# temperatur_sensor_childboard_v1.net
KiCad netlist of a schematic drawn in EAGLE
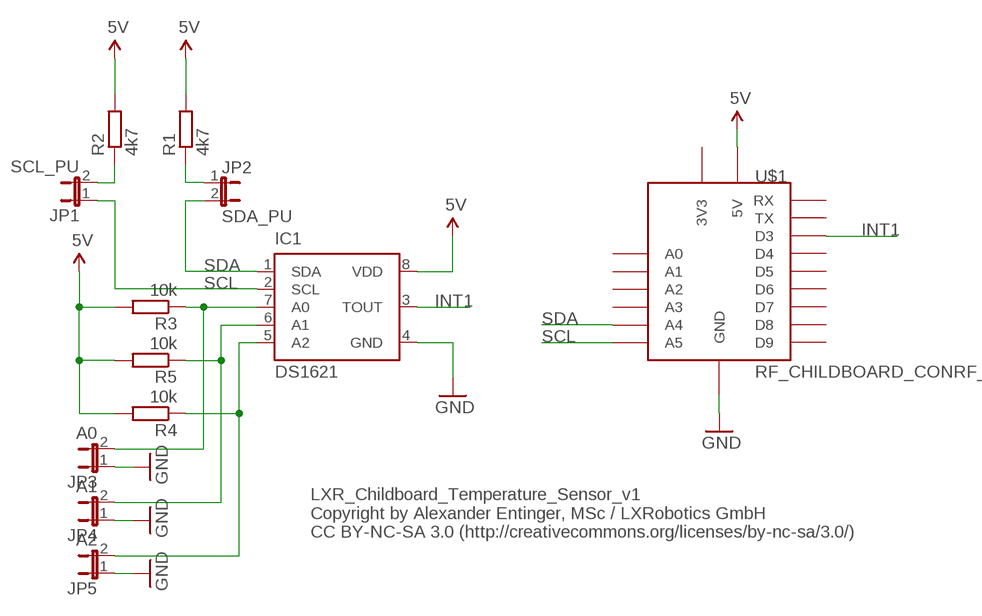
[diagram p0: schematic, sheet 1]

(export (version "E")
  (design (tool "Eeschema 10.0.6"))
  (components
    (comp (ref "IC1")
      (value "DS1621")
      (footprint "eagle-import:DIL08")
      (libsource (lib "eagle-import") (part "DS1621"))
    )
    (comp (ref "JP1")
      (value "SCL_PU")
      (footprint "eagle-import:JP1")
      (libsource (lib "eagle-import") (part "JP1E"))
    )
    (comp (ref "JP2")
      (value "SDA_PU")
      (footprint "eagle-import:JP1")
      (libsource (lib "eagle-import") (part "JP1E"))
    )
    (comp (ref "JP3")
      (value "A0")
      (footprint "eagle-import:JP1")
      (libsource (lib "eagle-import") (part "JP1E"))
    )
    (comp (ref "JP4")
      (value "A1")
      (footprint "eagle-import:JP1")
      (libsource (lib "eagle-import") (part "JP1E"))
    )
    (comp (ref "JP5")
      (value "A2")
      (footprint "eagle-import:JP1")
      (libsource (lib "eagle-import") (part "JP1E"))
    )
    (comp (ref "R1")
      (value "4k7")
      (footprint "eagle-import:0207_7")
      (libsource (lib "eagle-import") (part "R-EU_0207/7"))
    )
    (comp (ref "R2")
      (value "4k7")
      (footprint "eagle-import:0207_7")
      (libsource (lib "eagle-import") (part "R-EU_0207/7"))
    )
    (comp (ref "R3")
      (value "10k")
      (footprint "eagle-import:0207_7")
      (libsource (lib "eagle-import") (part "R-EU_0207/7"))
    )
    (comp (ref "R4")
      (value "10k")
      (footprint "eagle-import:0207_7")
      (libsource (lib "eagle-import") (part "R-EU_0207/7"))
    )
    (comp (ref "R5")
      (value "10k")
      (footprint "eagle-import:0207_7")
      (libsource (lib "eagle-import") (part "R-EU_0207/7"))
    )
    (comp (ref "U$1")
      (value "RF_CHILDBOARD_CONRF_C")
      (footprint "eagle-import:RF_CHILDBOARD_CON")
      (libsource (lib "eagle-import") (part "RF_CHILDBOARD_CONRF_C"))
    )
  )
  (nets
    (net (code "1") (name "/INT1") (class "Default")
      (node (ref "IC1") (pin "3") (pinfunction "TOUT_3") (pintype "output"))
      (node (ref "U$1") (pin "D3") (pinfunction "D3_D3") (pintype "bidirectional"))
    )
    (net (code "2") (name "/SCL") (class "Default")
      (node (ref "IC1") (pin "2") (pinfunction "SCL_2") (pintype "input"))
      (node (ref "JP1") (pin "1") (pinfunction "1_1") (pintype "passive"))
      (node (ref "U$1") (pin "A5") (pinfunction "A5_A5") (pintype "bidirectional"))
    )
    (net (code "3") (name "/SDA") (class "Default")
      (node (ref "IC1") (pin "1") (pinfunction "SDA_1") (pintype "bidirectional"))
      (node (ref "JP2") (pin "2") (pinfunction "2_2") (pintype "passive"))
      (node (ref "U$1") (pin "A4") (pinfunction "A4_A4") (pintype "bidirectional"))
    )
    (net (code "4") (name "5V") (class "Default")
      (node (ref "IC1") (pin "8") (pinfunction "VDD_8") (pintype "power_in"))
      (node (ref "R1") (pin "2") (pinfunction "2_2") (pintype "passive"))
      (node (ref "R2") (pin "2") (pinfunction "2_2") (pintype "passive"))
      (node (ref "R3") (pin "2") (pinfunction "2_2") (pintype "passive"))
      (node (ref "R4") (pin "2") (pinfunction "2_2") (pintype "passive"))
      (node (ref "R5") (pin "2") (pinfunction "2_2") (pintype "passive"))
      (node (ref "U$1") (pin "5V") (pinfunction "5V_5V") (pintype "bidirectional"))
    )
    (net (code "5") (name "GND") (class "Default")
      (node (ref "IC1") (pin "4") (pinfunction "GND_4") (pintype "power_in"))
      (node (ref "JP3") (pin "1") (pinfunction "1_1") (pintype "passive"))
      (node (ref "JP4") (pin "1") (pinfunction "1_1") (pintype "passive"))
      (node (ref "JP5") (pin "1") (pinfunction "1_1") (pintype "passive"))
      (node (ref "U$1") (pin "GND") (pinfunction "GND_GND") (pintype "bidirectional"))
      (node (ref "U$1") (pin "GND1") (pinfunction "GND_GND1") (pintype "bidirectional"))
      (node (ref "U$1") (pin "GND2") (pinfunction "GND_GND2") (pintype "bidirectional"))
    )
    (net (code "6") (name "Net-(IC1-A0)") (class "Default")
      (node (ref "IC1") (pin "7") (pinfunction "A0_7") (pintype "input"))
      (node (ref "JP3") (pin "2") (pinfunction "2_2") (pintype "passive"))
      (node (ref "R3") (pin "1") (pinfunction "1_1") (pintype "passive"))
    )
    (net (code "7") (name "Net-(IC1-A1)") (class "Default")
      (node (ref "IC1") (pin "6") (pinfunction "A1_6") (pintype "input"))
      (node (ref "JP4") (pin "2") (pinfunction "2_2") (pintype "passive"))
      (node (ref "R5") (pin "1") (pinfunction "1_1") (pintype "passive"))
    )
    (net (code "8") (name "Net-(IC1-A2)") (class "Default")
      (node (ref "IC1") (pin "5") (pinfunction "A2_5") (pintype "input"))
      (node (ref "JP5") (pin "2") (pinfunction "2_2") (pintype "passive"))
      (node (ref "R4") (pin "1") (pinfunction "1_1") (pintype "passive"))
    )
    (net (code "9") (name "Net-(JP1-Pad2)") (class "Default")
      (node (ref "JP1") (pin "2") (pinfunction "2_2") (pintype "passive"))
      (node (ref "R2") (pin "1") (pinfunction "1_1") (pintype "passive"))
    )
    (net (code "10") (name "Net-(JP2-Pad1)") (class "Default")
      (node (ref "JP2") (pin "1") (pinfunction "1_1") (pintype "passive"))
      (node (ref "R1") (pin "1") (pinfunction "1_1") (pintype "passive"))
    )
    (net (code "11") (name "unconnected-(U$1-Pad3V3)") (class "Default")
      (node (ref "U$1") (pin "3V3") (pinfunction "3V3_3V3") (pintype "bidirectional"))
    )
    (net (code "12") (name "unconnected-(U$1-PadA0)") (class "Default")
      (node (ref "U$1") (pin "A0") (pinfunction "A0_A0") (pintype "bidirectional"))
    )
    (net (code "13") (name "unconnected-(U$1-PadA1)") (class "Default")
      (node (ref "U$1") (pin "A1") (pinfunction "A1_A1") (pintype "bidirectional"))
    )
    (net (code "14") (name "unconnected-(U$1-PadA2)") (class "Default")
      (node (ref "U$1") (pin "A2") (pinfunction "A2_A2") (pintype "bidirectional"))
    )
    (net (code "15") (name "unconnected-(U$1-PadA3)") (class "Default")
      (node (ref "U$1") (pin "A3") (pinfunction "A3_A3") (pintype "bidirectional"))
    )
    (net (code "16") (name "unconnected-(U$1-PadD4)") (class "Default")
      (node (ref "U$1") (pin "D4") (pinfunction "D4_D4") (pintype "bidirectional"))
    )
    (net (code "17") (name "unconnected-(U$1-PadD5)") (class "Default")
      (node (ref "U$1") (pin "D5") (pinfunction "D5_D5") (pintype "bidirectional"))
    )
    (net (code "18") (name "unconnected-(U$1-PadD6)") (class "Default")
      (node (ref "U$1") (pin "D6") (pinfunction "D6_D6") (pintype "bidirectional"))
    )
    (net (code "19") (name "unconnected-(U$1-PadD7)") (class "Default")
      (node (ref "U$1") (pin "D7") (pinfunction "D7_D7") (pintype "bidirectional"))
    )
    (net (code "20") (name "unconnected-(U$1-PadD8)") (class "Default")
      (node (ref "U$1") (pin "D8") (pinfunction "D8_D8") (pintype "bidirectional"))
    )
    (net (code "21") (name "unconnected-(U$1-PadD9)") (class "Default")
      (node (ref "U$1") (pin "D9") (pinfunction "D9_D9") (pintype "bidirectional"))
    )
    (net (code "22") (name "unconnected-(U$1-PadRX)") (class "Default")
      (node (ref "U$1") (pin "RX") (pinfunction "RX_RX") (pintype "bidirectional"))
    )
    (net (code "23") (name "unconnected-(U$1-PadTX)") (class "Default")
      (node (ref "U$1") (pin "TX") (pinfunction "TX_TX") (pintype "bidirectional"))
    )
  )
)
